# Sheet1.net
KiCad netlist of a schematic drawn in Altium Designer
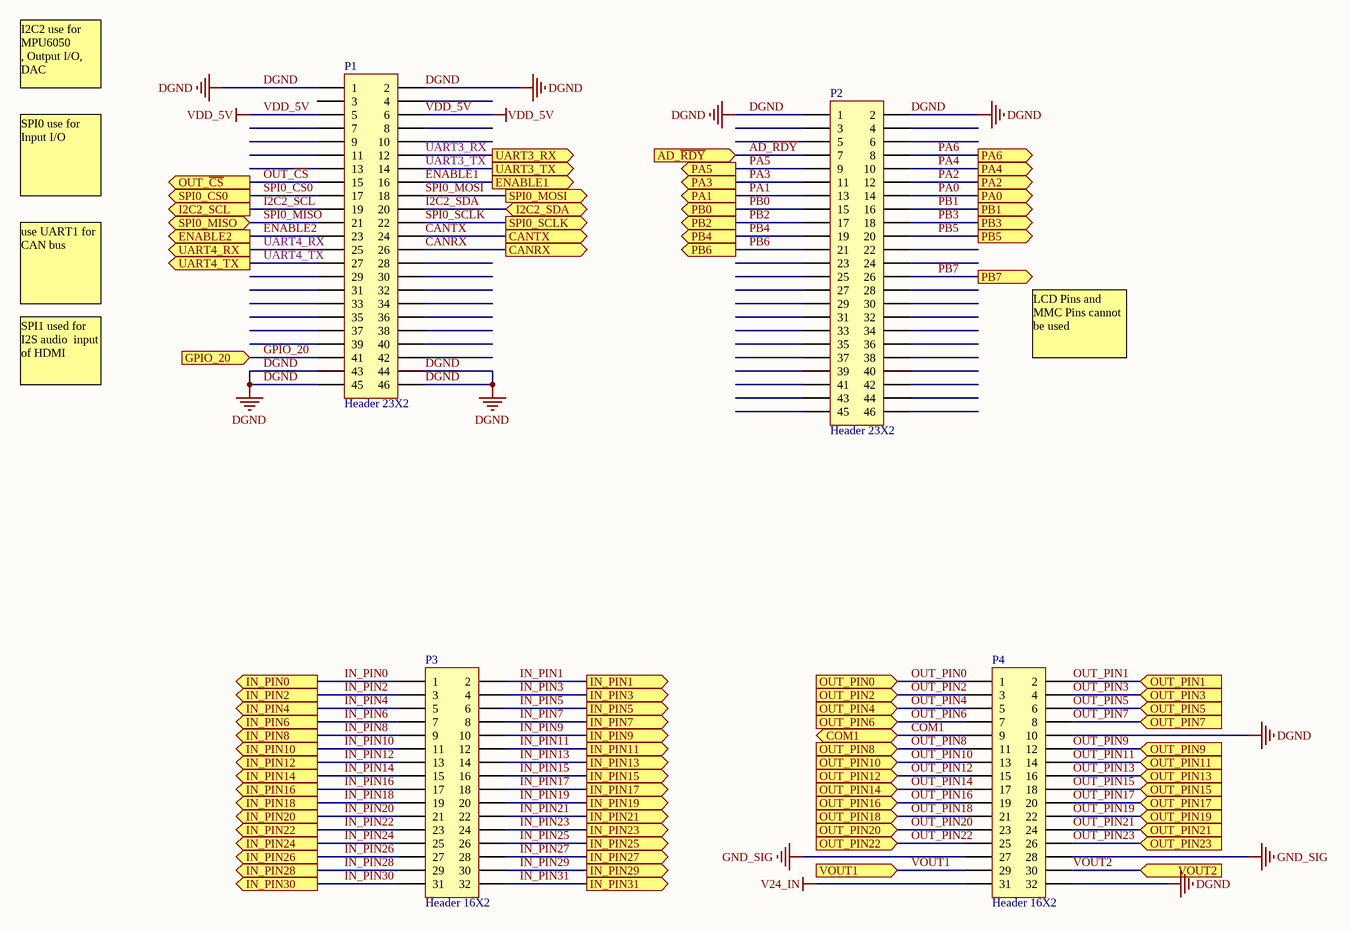
[diagram p0: Sheet1.SchDoc]

(export (version "E")
  (design (tool "Eeschema 10.0.6"))
  (components
    (comp (ref "P1")
      (value "Header 23X2")
      (footprint "HDR2X23")
      (description "Header, 23-Pin, Dual row")
      (fields (field (name "PUBLISHER") "Altium Limited"))
      (libsource (lib "dolphi_ecs") (part "Header 23X2"))
    )
    (comp (ref "P2")
      (value "Header 23X2")
      (footprint "HDR2X23")
      (description "Header, 23-Pin, Dual row")
      (fields (field (name "PUBLISHER") "Altium Limited"))
      (libsource (lib "dolphi_ecs") (part "Header 23X2"))
    )
    (comp (ref "P3")
      (value "Header 16X2")
      (footprint "CON16X2-8.5")
      (description "Header, 16-Pin, Dual row")
      (fields (field (name "PUBLISHER") "Altium Limited"))
      (libsource (lib "Miscellaneous Connectors") (part "Header 16X2"))
    )
    (comp (ref "P4")
      (value "Header 16X2")
      (footprint "CON16X2-8.5")
      (description "Header, 16-Pin, Dual row")
      (fields (field (name "PUBLISHER") "Altium Limited"))
      (libsource (lib "Miscellaneous Connectors") (part "Header 16X2"))
    )
  )
  (nets
    (net (code "1") (name "/AD_~{RDY}") (class "Default")
      (node (ref "P2") (pin "7") (pinfunction "7_7") (pintype "passive"))
    )
    (net (code "2") (name "/CANRX") (class "Default")
      (node (ref "P1") (pin "26") (pinfunction "26_26") (pintype "passive"))
    )
    (net (code "3") (name "/CANTX") (class "Default")
      (node (ref "P1") (pin "24") (pinfunction "24_24") (pintype "passive"))
    )
    (net (code "4") (name "/COM1") (class "Default")
      (node (ref "P4") (pin "9") (pinfunction "9_9") (pintype "passive"))
    )
    (net (code "5") (name "/ENABLE1") (class "Default")
      (node (ref "P1") (pin "16") (pinfunction "16_16") (pintype "passive"))
    )
    (net (code "6") (name "/ENABLE2") (class "Default")
      (node (ref "P1") (pin "23") (pinfunction "23_23") (pintype "passive"))
    )
    (net (code "7") (name "/GPIO_20") (class "Default")
      (node (ref "P1") (pin "41") (pinfunction "41_41") (pintype "passive"))
    )
    (net (code "8") (name "/I2C2_SCL") (class "Default")
      (node (ref "P1") (pin "19") (pinfunction "19_19") (pintype "passive"))
    )
    (net (code "9") (name "/I2C2_SDA") (class "Default")
      (node (ref "P1") (pin "20") (pinfunction "20_20") (pintype "passive"))
    )
    (net (code "10") (name "/IN_PIN0") (class "Default")
      (node (ref "P3") (pin "1") (pinfunction "1_1") (pintype "passive"))
    )
    (net (code "11") (name "/IN_PIN1") (class "Default")
      (node (ref "P3") (pin "2") (pinfunction "2_2") (pintype "passive"))
    )
    (net (code "12") (name "/IN_PIN2") (class "Default")
      (node (ref "P3") (pin "3") (pinfunction "3_3") (pintype "passive"))
    )
    (net (code "13") (name "/IN_PIN3") (class "Default")
      (node (ref "P3") (pin "4") (pinfunction "4_4") (pintype "passive"))
    )
    (net (code "14") (name "/IN_PIN4") (class "Default")
      (node (ref "P3") (pin "5") (pinfunction "5_5") (pintype "passive"))
    )
    (net (code "15") (name "/IN_PIN5") (class "Default")
      (node (ref "P3") (pin "6") (pinfunction "6_6") (pintype "passive"))
    )
    (net (code "16") (name "/IN_PIN6") (class "Default")
      (node (ref "P3") (pin "7") (pinfunction "7_7") (pintype "passive"))
    )
    (net (code "17") (name "/IN_PIN7") (class "Default")
      (node (ref "P3") (pin "8") (pinfunction "8_8") (pintype "passive"))
    )
    (net (code "18") (name "/IN_PIN8") (class "Default")
      (node (ref "P3") (pin "9") (pinfunction "9_9") (pintype "passive"))
    )
    (net (code "19") (name "/IN_PIN9") (class "Default")
      (node (ref "P3") (pin "10") (pinfunction "10_10") (pintype "passive"))
    )
    (net (code "20") (name "/IN_PIN10") (class "Default")
      (node (ref "P3") (pin "11") (pinfunction "11_11") (pintype "passive"))
    )
    (net (code "21") (name "/IN_PIN11") (class "Default")
      (node (ref "P3") (pin "12") (pinfunction "12_12") (pintype "passive"))
    )
    (net (code "22") (name "/IN_PIN12") (class "Default")
      (node (ref "P3") (pin "13") (pinfunction "13_13") (pintype "passive"))
    )
    (net (code "23") (name "/IN_PIN13") (class "Default")
      (node (ref "P3") (pin "14") (pinfunction "14_14") (pintype "passive"))
    )
    (net (code "24") (name "/IN_PIN14") (class "Default")
      (node (ref "P3") (pin "15") (pinfunction "15_15") (pintype "passive"))
    )
    (net (code "25") (name "/IN_PIN15") (class "Default")
      (node (ref "P3") (pin "16") (pinfunction "16_16") (pintype "passive"))
    )
    (net (code "26") (name "/IN_PIN16") (class "Default")
      (node (ref "P3") (pin "17") (pinfunction "17_17") (pintype "passive"))
    )
    (net (code "27") (name "/IN_PIN17") (class "Default")
      (node (ref "P3") (pin "18") (pinfunction "18_18") (pintype "passive"))
    )
    (net (code "28") (name "/IN_PIN18") (class "Default")
      (node (ref "P3") (pin "19") (pinfunction "19_19") (pintype "passive"))
    )
    (net (code "29") (name "/IN_PIN19") (class "Default")
      (node (ref "P3") (pin "20") (pinfunction "20_20") (pintype "passive"))
    )
    (net (code "30") (name "/IN_PIN20") (class "Default")
      (node (ref "P3") (pin "21") (pinfunction "21_21") (pintype "passive"))
    )
    (net (code "31") (name "/IN_PIN21") (class "Default")
      (node (ref "P3") (pin "22") (pinfunction "22_22") (pintype "passive"))
    )
    (net (code "32") (name "/IN_PIN22") (class "Default")
      (node (ref "P3") (pin "23") (pinfunction "23_23") (pintype "passive"))
    )
    (net (code "33") (name "/IN_PIN23") (class "Default")
      (node (ref "P3") (pin "24") (pinfunction "24_24") (pintype "passive"))
    )
    (net (code "34") (name "/IN_PIN24") (class "Default")
      (node (ref "P3") (pin "25") (pinfunction "25_25") (pintype "passive"))
    )
    (net (code "35") (name "/IN_PIN25") (class "Default")
      (node (ref "P3") (pin "26") (pinfunction "26_26") (pintype "passive"))
    )
    (net (code "36") (name "/IN_PIN26") (class "Default")
      (node (ref "P3") (pin "27") (pinfunction "27_27") (pintype "passive"))
    )
    (net (code "37") (name "/IN_PIN27") (class "Default")
      (node (ref "P3") (pin "28") (pinfunction "28_28") (pintype "passive"))
    )
    (net (code "38") (name "/IN_PIN28") (class "Default")
      (node (ref "P3") (pin "29") (pinfunction "29_29") (pintype "passive"))
    )
    (net (code "39") (name "/IN_PIN29") (class "Default")
      (node (ref "P3") (pin "30") (pinfunction "30_30") (pintype "passive"))
    )
    (net (code "40") (name "/IN_PIN30") (class "Default")
      (node (ref "P3") (pin "31") (pinfunction "31_31") (pintype "passive"))
    )
    (net (code "41") (name "/IN_PIN31") (class "Default")
      (node (ref "P3") (pin "32") (pinfunction "32_32") (pintype "passive"))
    )
    (net (code "42") (name "/OUT_PIN0") (class "Default")
      (node (ref "P4") (pin "1") (pinfunction "1_1") (pintype "passive"))
    )
    (net (code "43") (name "/OUT_PIN1") (class "Default")
      (node (ref "P4") (pin "2") (pinfunction "2_2") (pintype "passive"))
    )
    (net (code "44") (name "/OUT_PIN2") (class "Default")
      (node (ref "P4") (pin "3") (pinfunction "3_3") (pintype "passive"))
    )
    (net (code "45") (name "/OUT_PIN3") (class "Default")
      (node (ref "P4") (pin "4") (pinfunction "4_4") (pintype "passive"))
    )
    (net (code "46") (name "/OUT_PIN4") (class "Default")
      (node (ref "P4") (pin "5") (pinfunction "5_5") (pintype "passive"))
    )
    (net (code "47") (name "/OUT_PIN5") (class "Default")
      (node (ref "P4") (pin "6") (pinfunction "6_6") (pintype "passive"))
    )
    (net (code "48") (name "/OUT_PIN6") (class "Default")
      (node (ref "P4") (pin "7") (pinfunction "7_7") (pintype "passive"))
    )
    (net (code "49") (name "/OUT_PIN7") (class "Default")
      (node (ref "P4") (pin "8") (pinfunction "8_8") (pintype "passive"))
    )
    (net (code "50") (name "/OUT_PIN8") (class "Default")
      (node (ref "P4") (pin "11") (pinfunction "11_11") (pintype "passive"))
    )
    (net (code "51") (name "/OUT_PIN9") (class "Default")
      (node (ref "P4") (pin "12") (pinfunction "12_12") (pintype "passive"))
    )
    (net (code "52") (name "/OUT_PIN10") (class "Default")
      (node (ref "P4") (pin "13") (pinfunction "13_13") (pintype "passive"))
    )
    (net (code "53") (name "/OUT_PIN11") (class "Default")
      (node (ref "P4") (pin "14") (pinfunction "14_14") (pintype "passive"))
    )
    (net (code "54") (name "/OUT_PIN12") (class "Default")
      (node (ref "P4") (pin "15") (pinfunction "15_15") (pintype "passive"))
    )
    (net (code "55") (name "/OUT_PIN13") (class "Default")
      (node (ref "P4") (pin "16") (pinfunction "16_16") (pintype "passive"))
    )
    (net (code "56") (name "/OUT_PIN14") (class "Default")
      (node (ref "P4") (pin "17") (pinfunction "17_17") (pintype "passive"))
    )
    (net (code "57") (name "/OUT_PIN15") (class "Default")
      (node (ref "P4") (pin "18") (pinfunction "18_18") (pintype "passive"))
    )
    (net (code "58") (name "/OUT_PIN16") (class "Default")
      (node (ref "P4") (pin "19") (pinfunction "19_19") (pintype "passive"))
    )
    (net (code "59") (name "/OUT_PIN17") (class "Default")
      (node (ref "P4") (pin "20") (pinfunction "20_20") (pintype "passive"))
    )
    (net (code "60") (name "/OUT_PIN18") (class "Default")
      (node (ref "P4") (pin "21") (pinfunction "21_21") (pintype "passive"))
    )
    (net (code "61") (name "/OUT_PIN19") (class "Default")
      (node (ref "P4") (pin "22") (pinfunction "22_22") (pintype "passive"))
    )
    (net (code "62") (name "/OUT_PIN20") (class "Default")
      (node (ref "P4") (pin "23") (pinfunction "23_23") (pintype "passive"))
    )
    (net (code "63") (name "/OUT_PIN21") (class "Default")
      (node (ref "P4") (pin "24") (pinfunction "24_24") (pintype "passive"))
    )
    (net (code "64") (name "/OUT_PIN22") (class "Default")
      (node (ref "P4") (pin "25") (pinfunction "25_25") (pintype "passive"))
    )
    (net (code "65") (name "/OUT_PIN23") (class "Default")
      (node (ref "P4") (pin "26") (pinfunction "26_26") (pintype "passive"))
    )
    (net (code "66") (name "/OUT_~{CS}") (class "Default")
      (node (ref "P1") (pin "15") (pinfunction "15_15") (pintype "passive"))
    )
    (net (code "67") (name "/PA0") (class "Default")
      (node (ref "P2") (pin "14") (pinfunction "14_14") (pintype "passive"))
    )
    (net (code "68") (name "/PA1") (class "Default")
      (node (ref "P2") (pin "13") (pinfunction "13_13") (pintype "passive"))
    )
    (net (code "69") (name "/PA2") (class "Default")
      (node (ref "P2") (pin "12") (pinfunction "12_12") (pintype "passive"))
    )
    (net (code "70") (name "/PA3") (class "Default")
      (node (ref "P2") (pin "11") (pinfunction "11_11") (pintype "passive"))
    )
    (net (code "71") (name "/PA4") (class "Default")
      (node (ref "P2") (pin "10") (pinfunction "10_10") (pintype "passive"))
    )
    (net (code "72") (name "/PA5") (class "Default")
      (node (ref "P2") (pin "9") (pinfunction "9_9") (pintype "passive"))
    )
    (net (code "73") (name "/PA6") (class "Default")
      (node (ref "P2") (pin "8") (pinfunction "8_8") (pintype "passive"))
    )
    (net (code "74") (name "/PB0") (class "Default")
      (node (ref "P2") (pin "15") (pinfunction "15_15") (pintype "passive"))
    )
    (net (code "75") (name "/PB1") (class "Default")
      (node (ref "P2") (pin "16") (pinfunction "16_16") (pintype "passive"))
    )
    (net (code "76") (name "/PB2") (class "Default")
      (node (ref "P2") (pin "17") (pinfunction "17_17") (pintype "passive"))
    )
    (net (code "77") (name "/PB3") (class "Default")
      (node (ref "P2") (pin "18") (pinfunction "18_18") (pintype "passive"))
    )
    (net (code "78") (name "/PB4") (class "Default")
      (node (ref "P2") (pin "19") (pinfunction "19_19") (pintype "passive"))
    )
    (net (code "79") (name "/PB5") (class "Default")
      (node (ref "P2") (pin "20") (pinfunction "20_20") (pintype "passive"))
    )
    (net (code "80") (name "/PB6") (class "Default")
      (node (ref "P2") (pin "21") (pinfunction "21_21") (pintype "passive"))
    )
    (net (code "81") (name "/PB7") (class "Default")
      (node (ref "P2") (pin "26") (pinfunction "26_26") (pintype "passive"))
    )
    (net (code "82") (name "/SPI0_CS0") (class "Default")
      (node (ref "P1") (pin "17") (pinfunction "17_17") (pintype "passive"))
    )
    (net (code "83") (name "/SPI0_MISO") (class "Default")
      (node (ref "P1") (pin "21") (pinfunction "21_21") (pintype "passive"))
    )
    (net (code "84") (name "/SPI0_MOSI") (class "Default")
      (node (ref "P1") (pin "18") (pinfunction "18_18") (pintype "passive"))
    )
    (net (code "85") (name "/SPI0_SCLK") (class "Default")
      (node (ref "P1") (pin "22") (pinfunction "22_22") (pintype "passive"))
    )
    (net (code "86") (name "/UART3_RX") (class "Default")
      (node (ref "P1") (pin "12") (pinfunction "12_12") (pintype "passive"))
    )
    (net (code "87") (name "/UART3_TX") (class "Default")
      (node (ref "P1") (pin "14") (pinfunction "14_14") (pintype "passive"))
    )
    (net (code "88") (name "/UART4_RX") (class "Default")
      (node (ref "P1") (pin "25") (pinfunction "25_25") (pintype "passive"))
    )
    (net (code "89") (name "/UART4_TX") (class "Default")
      (node (ref "P1") (pin "27") (pinfunction "27_27") (pintype "passive"))
    )
    (net (code "90") (name "/VOUT1") (class "Default")
      (node (ref "P4") (pin "29") (pinfunction "29_29") (pintype "passive"))
    )
    (net (code "91") (name "/VOUT2") (class "Default")
      (node (ref "P4") (pin "30") (pinfunction "30_30") (pintype "passive"))
    )
    (net (code "92") (name "DGND") (class "Default")
      (node (ref "P1") (pin "1") (pinfunction "1_1") (pintype "passive"))
      (node (ref "P1") (pin "2") (pinfunction "2_2") (pintype "passive"))
      (node (ref "P1") (pin "43") (pinfunction "43_43") (pintype "passive"))
      (node (ref "P1") (pin "44") (pinfunction "44_44") (pintype "passive"))
      (node (ref "P1") (pin "45") (pinfunction "45_45") (pintype "passive"))
      (node (ref "P1") (pin "46") (pinfunction "46_46") (pintype "passive"))
      (node (ref "P2") (pin "1") (pinfunction "1_1") (pintype "passive"))
      (node (ref "P2") (pin "2") (pinfunction "2_2") (pintype "passive"))
      (node (ref "P4") (pin "10") (pinfunction "10_10") (pintype "passive"))
      (node (ref "P4") (pin "32") (pinfunction "32_32") (pintype "passive"))
    )
    (net (code "93") (name "GND_SIG") (class "Default")
      (node (ref "P4") (pin "27") (pinfunction "27_27") (pintype "passive"))
      (node (ref "P4") (pin "28") (pinfunction "28_28") (pintype "passive"))
    )
    (net (code "94") (name "V24_IN") (class "Default")
      (node (ref "P4") (pin "31") (pinfunction "31_31") (pintype "passive"))
    )
    (net (code "95") (name "VDD_5V") (class "Default")
      (node (ref "P1") (pin "5") (pinfunction "5_5") (pintype "passive"))
      (node (ref "P1") (pin "6") (pinfunction "6_6") (pintype "passive"))
    )
    (net (code "96") (name "unconnected-(P1-Pad3)") (class "Default")
      (node (ref "P1") (pin "3") (pinfunction "3_3") (pintype "passive"))
    )
    (net (code "97") (name "unconnected-(P1-Pad4)") (class "Default")
      (node (ref "P1") (pin "4") (pinfunction "4_4") (pintype "passive"))
    )
    (net (code "98") (name "unconnected-(P1-Pad7)") (class "Default")
      (node (ref "P1") (pin "7") (pinfunction "7_7") (pintype "passive"))
    )
    (net (code "99") (name "unconnected-(P1-Pad8)") (class "Default")
      (node (ref "P1") (pin "8") (pinfunction "8_8") (pintype "passive"))
    )
    (net (code "100") (name "unconnected-(P1-Pad9)") (class "Default")
      (node (ref "P1") (pin "9") (pinfunction "9_9") (pintype "passive"))
    )
    (net (code "101") (name "unconnected-(P1-Pad10)") (class "Default")
      (node (ref "P1") (pin "10") (pinfunction "10_10") (pintype "passive"))
    )
    (net (code "102") (name "unconnected-(P1-Pad11)") (class "Default")
      (node (ref "P1") (pin "11") (pinfunction "11_11") (pintype "passive"))
    )
    (net (code "103") (name "unconnected-(P1-Pad13)") (class "Default")
      (node (ref "P1") (pin "13") (pinfunction "13_13") (pintype "passive"))
    )
    (net (code "104") (name "unconnected-(P1-Pad28)") (class "Default")
      (node (ref "P1") (pin "28") (pinfunction "28_28") (pintype "passive"))
    )
    (net (code "105") (name "unconnected-(P1-Pad29)") (class "Default")
      (node (ref "P1") (pin "29") (pinfunction "29_29") (pintype "passive"))
    )
    (net (code "106") (name "unconnected-(P1-Pad30)") (class "Default")
      (node (ref "P1") (pin "30") (pinfunction "30_30") (pintype "passive"))
    )
    (net (code "107") (name "unconnected-(P1-Pad31)") (class "Default")
      (node (ref "P1") (pin "31") (pinfunction "31_31") (pintype "passive"))
    )
    (net (code "108") (name "unconnected-(P1-Pad32)") (class "Default")
      (node (ref "P1") (pin "32") (pinfunction "32_32") (pintype "passive"))
    )
    (net (code "109") (name "unconnected-(P1-Pad33)") (class "Default")
      (node (ref "P1") (pin "33") (pinfunction "33_33") (pintype "passive"))
    )
    (net (code "110") (name "unconnected-(P1-Pad34)") (class "Default")
      (node (ref "P1") (pin "34") (pinfunction "34_34") (pintype "passive"))
    )
    (net (code "111") (name "unconnected-(P1-Pad35)") (class "Default")
      (node (ref "P1") (pin "35") (pinfunction "35_35") (pintype "passive"))
    )
    (net (code "112") (name "unconnected-(P1-Pad36)") (class "Default")
      (node (ref "P1") (pin "36") (pinfunction "36_36") (pintype "passive"))
    )
    (net (code "113") (name "unconnected-(P1-Pad37)") (class "Default")
      (node (ref "P1") (pin "37") (pinfunction "37_37") (pintype "passive"))
    )
    (net (code "114") (name "unconnected-(P1-Pad38)") (class "Default")
      (node (ref "P1") (pin "38") (pinfunction "38_38") (pintype "passive"))
    )
    (net (code "115") (name "unconnected-(P1-Pad39)") (class "Default")
      (node (ref "P1") (pin "39") (pinfunction "39_39") (pintype "passive"))
    )
    (net (code "116") (name "unconnected-(P1-Pad40)") (class "Default")
      (node (ref "P1") (pin "40") (pinfunction "40_40") (pintype "passive"))
    )
    (net (code "117") (name "unconnected-(P1-Pad42)") (class "Default")
      (node (ref "P1") (pin "42") (pinfunction "42_42") (pintype "passive"))
    )
    (net (code "118") (name "unconnected-(P2-Pad3)") (class "Default")
      (node (ref "P2") (pin "3") (pinfunction "3_3") (pintype "passive"))
    )
    (net (code "119") (name "unconnected-(P2-Pad4)") (class "Default")
      (node (ref "P2") (pin "4") (pinfunction "4_4") (pintype "passive"))
    )
    (net (code "120") (name "unconnected-(P2-Pad5)") (class "Default")
      (node (ref "P2") (pin "5") (pinfunction "5_5") (pintype "passive"))
    )
    (net (code "121") (name "unconnected-(P2-Pad6)") (class "Default")
      (node (ref "P2") (pin "6") (pinfunction "6_6") (pintype "passive"))
    )
    (net (code "122") (name "unconnected-(P2-Pad22)") (class "Default")
      (node (ref "P2") (pin "22") (pinfunction "22_22") (pintype "passive"))
    )
    (net (code "123") (name "unconnected-(P2-Pad23)") (class "Default")
      (node (ref "P2") (pin "23") (pinfunction "23_23") (pintype "passive"))
    )
    (net (code "124") (name "unconnected-(P2-Pad24)") (class "Default")
      (node (ref "P2") (pin "24") (pinfunction "24_24") (pintype "passive"))
    )
    (net (code "125") (name "unconnected-(P2-Pad25)") (class "Default")
      (node (ref "P2") (pin "25") (pinfunction "25_25") (pintype "passive"))
    )
    (net (code "126") (name "unconnected-(P2-Pad27)") (class "Default")
      (node (ref "P2") (pin "27") (pinfunction "27_27") (pintype "passive"))
    )
    (net (code "127") (name "unconnected-(P2-Pad28)") (class "Default")
      (node (ref "P2") (pin "28") (pinfunction "28_28") (pintype "passive"))
    )
    (net (code "128") (name "unconnected-(P2-Pad29)") (class "Default")
      (node (ref "P2") (pin "29") (pinfunction "29_29") (pintype "passive"))
    )
    (net (code "129") (name "unconnected-(P2-Pad30)") (class "Default")
      (node (ref "P2") (pin "30") (pinfunction "30_30") (pintype "passive"))
    )
    (net (code "130") (name "unconnected-(P2-Pad31)") (class "Default")
      (node (ref "P2") (pin "31") (pinfunction "31_31") (pintype "passive"))
    )
    (net (code "131") (name "unconnected-(P2-Pad32)") (class "Default")
      (node (ref "P2") (pin "32") (pinfunction "32_32") (pintype "passive"))
    )
    (net (code "132") (name "unconnected-(P2-Pad33)") (class "Default")
      (node (ref "P2") (pin "33") (pinfunction "33_33") (pintype "passive"))
    )
    (net (code "133") (name "unconnected-(P2-Pad34)") (class "Default")
      (node (ref "P2") (pin "34") (pinfunction "34_34") (pintype "passive"))
    )
    (net (code "134") (name "unconnected-(P2-Pad35)") (class "Default")
      (node (ref "P2") (pin "35") (pinfunction "35_35") (pintype "passive"))
    )
    (net (code "135") (name "unconnected-(P2-Pad36)") (class "Default")
      (node (ref "P2") (pin "36") (pinfunction "36_36") (pintype "passive"))
    )
    (net (code "136") (name "unconnected-(P2-Pad37)") (class "Default")
      (node (ref "P2") (pin "37") (pinfunction "37_37") (pintype "passive"))
    )
    (net (code "137") (name "unconnected-(P2-Pad38)") (class "Default")
      (node (ref "P2") (pin "38") (pinfunction "38_38") (pintype "passive"))
    )
    (net (code "138") (name "unconnected-(P2-Pad39)") (class "Default")
      (node (ref "P2") (pin "39") (pinfunction "39_39") (pintype "passive"))
    )
    (net (code "139") (name "unconnected-(P2-Pad40)") (class "Default")
      (node (ref "P2") (pin "40") (pinfunction "40_40") (pintype "passive"))
    )
    (net (code "140") (name "unconnected-(P2-Pad41)") (class "Default")
      (node (ref "P2") (pin "41") (pinfunction "41_41") (pintype "passive"))
    )
    (net (code "141") (name "unconnected-(P2-Pad42)") (class "Default")
      (node (ref "P2") (pin "42") (pinfunction "42_42") (pintype "passive"))
    )
    (net (code "142") (name "unconnected-(P2-Pad43)") (class "Default")
      (node (ref "P2") (pin "43") (pinfunction "43_43") (pintype "passive"))
    )
    (net (code "143") (name "unconnected-(P2-Pad44)") (class "Default")
      (node (ref "P2") (pin "44") (pinfunction "44_44") (pintype "passive"))
    )
    (net (code "144") (name "unconnected-(P2-Pad45)") (class "Default")
      (node (ref "P2") (pin "45") (pinfunction "45_45") (pintype "passive"))
    )
    (net (code "145") (name "unconnected-(P2-Pad46)") (class "Default")
      (node (ref "P2") (pin "46") (pinfunction "46_46") (pintype "passive"))
    )
  )
)
